# Battery_and_ANT.net
KiCad netlist of a schematic drawn in Altium Designer
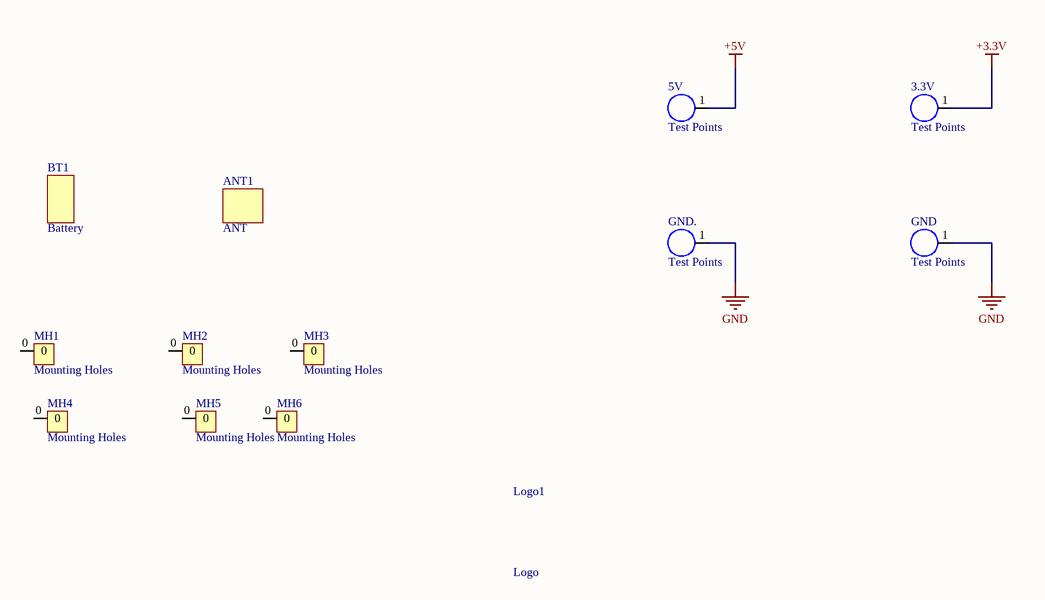
[diagram p0: Battery and ANT.SchDoc]

(export (version "E")
  (design (tool "Eeschema 10.0.6"))
  (components
    (comp (ref "3.3V")
      (value "Test Points")
      (footprint "Test Points")
      (libsource (lib "CV-R-BAP_V2.1.5") (part "Test Points"))
    )
    (comp (ref "5V")
      (value "Test Points")
      (footprint "Test Points")
      (libsource (lib "CV-R-BAP_V2.1.5") (part "Test Points"))
    )
    (comp (ref "ANT1") (value "ANT") (footprint "RFID_ANT") (libsource (lib "CV-R-BAP_V2.1.5") (part "ANT")))
    (comp (ref "BT1")
      (value "Battery")
      (footprint "Lipo_Battery")
      (libsource (lib "CV-R-BAP_V2.1.5") (part "Battery"))
    )
    (comp (ref "GND")
      (value "Test Points")
      (footprint "Test Points")
      (libsource (lib "CV-R-BAP_V2.1.5") (part "Test Points"))
    )
    (comp (ref "GND.")
      (value "Test Points")
      (footprint "Test Points")
      (libsource (lib "CV-R-BAP_V2.1.5") (part "Test Points"))
    )
    (comp (ref "Logo1") (value "Logo") (footprint "Logo") (libsource (lib "CV-R-BAP_V2.1.5") (part "Logo")))
    (comp (ref "MH1")
      (value "Mounting Holes")
      (footprint "PCBComponent_1")
      (libsource (lib "CV-R-BAP_V2.1.5") (part "Mounting Holes"))
    )
    (comp (ref "MH2")
      (value "Mounting Holes")
      (footprint "PCBComponent_1")
      (libsource (lib "CV-R-BAP_V2.1.5") (part "Mounting Holes"))
    )
    (comp (ref "MH3")
      (value "Mounting Holes")
      (footprint "PCBComponent_1")
      (libsource (lib "CV-R-BAP_V2.1.5") (part "Mounting Holes"))
    )
    (comp (ref "MH4")
      (value "Mounting Holes")
      (footprint "PCBComponent_1")
      (libsource (lib "CV-R-BAP_V2.1.5") (part "Mounting Holes"))
    )
    (comp (ref "MH5")
      (value "Mounting Holes")
      (footprint "PCBComponent_1")
      (libsource (lib "CV-R-BAP_V2.1.5") (part "Mounting Holes"))
    )
    (comp (ref "MH6")
      (value "Mounting Holes")
      (footprint "PCBComponent_1")
      (libsource (lib "CV-R-BAP_V2.1.5") (part "Mounting Holes"))
    )
  )
  (nets
    (net (code "1") (name "+3.3V") (class "Default")
      (node (ref "3.3V") (pin "1") (pinfunction "1_1") (pintype "passive"))
    )
    (net (code "2") (name "+5V") (class "Default")
      (node (ref "5V") (pin "1") (pinfunction "1_1") (pintype "passive"))
    )
    (net (code "3") (name "GND") (class "Default")
      (node (ref "GND") (pin "1") (pinfunction "1_1") (pintype "passive"))
      (node (ref "GND.") (pin "1") (pinfunction "1_1") (pintype "passive"))
    )
    (net (code "4") (name "unconnected-(MH1-Pad0)") (class "Default")
      (node (ref "MH1") (pin "0") (pinfunction "0_0") (pintype "passive"))
    )
    (net (code "5") (name "unconnected-(MH2-Pad0)") (class "Default")
      (node (ref "MH2") (pin "0") (pinfunction "0_0") (pintype "passive"))
    )
    (net (code "6") (name "unconnected-(MH3-Pad0)") (class "Default")
      (node (ref "MH3") (pin "0") (pinfunction "0_0") (pintype "passive"))
    )
    (net (code "7") (name "unconnected-(MH4-Pad0)") (class "Default")
      (node (ref "MH4") (pin "0") (pinfunction "0_0") (pintype "passive"))
    )
    (net (code "8") (name "unconnected-(MH5-Pad0)") (class "Default")
      (node (ref "MH5") (pin "0") (pinfunction "0_0") (pintype "passive"))
    )
    (net (code "9") (name "unconnected-(MH6-Pad0)") (class "Default")
      (node (ref "MH6") (pin "0") (pinfunction "0_0") (pintype "passive"))
    )
  )
)
